# MCU.net
KiCad netlist of a schematic drawn in Altium Designer
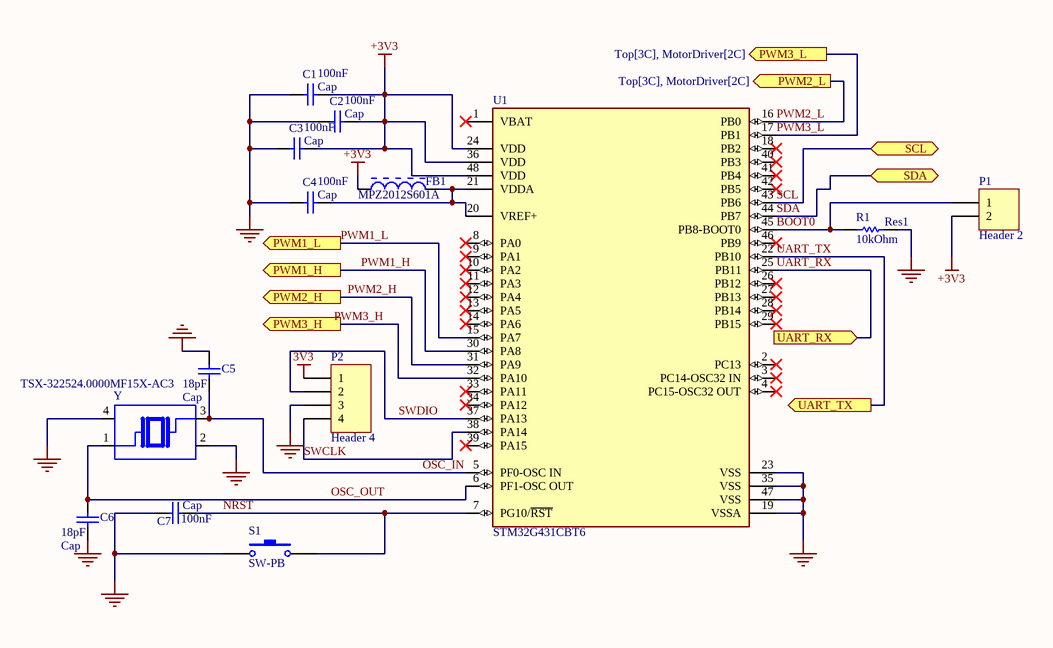
[diagram p0: MCU.SchDoc]

(export (version "E")
  (design (tool "Eeschema 10.0.6"))
  (components
    (comp (ref "C1")
      (value "Cap")
      (footprint "RAD-0.3")
      (description "Capacitor")
      (fields (field (name "ALTIUM_VALUE") "100nF") (field (name "PUBLISHER") "Altium Limited"))
      (libsource (lib "Miscellaneous Devices") (part "Cap"))
    )
    (comp (ref "C2")
      (value "Cap")
      (footprint "RAD-0.3")
      (description "Capacitor")
      (fields (field (name "ALTIUM_VALUE") "100nF") (field (name "PUBLISHER") "Altium Limited"))
      (libsource (lib "Miscellaneous Devices") (part "Cap"))
    )
    (comp (ref "C3")
      (value "Cap")
      (footprint "RAD-0.3")
      (description "Capacitor")
      (fields (field (name "ALTIUM_VALUE") "100nF") (field (name "PUBLISHER") "Altium Limited"))
      (libsource (lib "Miscellaneous Devices") (part "Cap"))
    )
    (comp (ref "C4")
      (value "Cap")
      (footprint "RAD-0.3")
      (description "Capacitor")
      (fields (field (name "ALTIUM_VALUE") "100nF") (field (name "PUBLISHER") "Altium Limited"))
      (libsource (lib "Miscellaneous Devices") (part "Cap"))
    )
    (comp (ref "C5")
      (value "Cap")
      (footprint "RAD-0.3")
      (description "Capacitor")
      (fields (field (name "ALTIUM_VALUE") "18pF") (field (name "PUBLISHER") "Altium Limited"))
      (libsource (lib "Miscellaneous Devices") (part "Cap"))
    )
    (comp (ref "C6")
      (value "Cap")
      (footprint "RAD-0.3")
      (description "Capacitor")
      (fields (field (name "ALTIUM_VALUE") "18pF") (field (name "PUBLISHER") "Altium Limited"))
      (libsource (lib "Miscellaneous Devices") (part "Cap"))
    )
    (comp (ref "C7")
      (value "Cap")
      (footprint "RAD-0.3")
      (description "Capacitor")
      (fields (field (name "ALTIUM_VALUE") "100nF") (field (name "PUBLISHER") "Altium Limited"))
      (libsource (lib "Miscellaneous Devices") (part "Cap"))
    )
    (comp (ref "FB1")
      (value "MPZ2012S601A")
      (footprint "TDK-MPZ2012_V")
      (fields (field (name "TOLERANCE") "25%") (field (name "MANUFACTURER") "TDK"))
      (libsource (lib "Altium Content Vault") (part "BEAD-2"))
    )
    (comp (ref "P1")
      (value "Header 2")
      (footprint "HDR1X2")
      (description "Header, 2-Pin")
      (fields (field (name "PUBLISHER") "Altium Limited"))
      (libsource (lib "Miscellaneous Connectors") (part "Header 2"))
    )
    (comp (ref "P2")
      (value "Header 4")
      (footprint "HDR1X4")
      (description "Header, 4-Pin")
      (fields (field (name "PUBLISHER") "Altium Limited"))
      (libsource (lib "Miscellaneous Connectors") (part "Header 4"))
    )
    (comp (ref "R1")
      (value "Res1")
      (footprint "AXIAL-0.3")
      (description "Resistor")
      (fields (field (name "ALTIUM_VALUE") "10kOhm") (field (name "PUBLISHER") "Altium Limited"))
      (libsource (lib "Miscellaneous Devices") (part "Res1"))
    )
    (comp (ref "S1")
      (value "SW-PB")
      (footprint "SPST-2")
      (description "Switch")
      (fields (field (name "PUBLISHER") "Altium Limited"))
      (libsource (lib "Miscellaneous Devices") (part "SW-PB"))
    )
    (comp (ref "U1")
      (value "STM32G431CBT6")
      (footprint "FP-LQFP48-5B-MFG")
      (description "MAINSTREAM ARM CORTEX-M4+ MCU 17")
      (fields
        (field (name "MANUFACTURER") "STMicroelectronics")
        (field (name "OCTOPART") "https://octopart.com/stm32g431cbt6-stmicroelectronics-98835224")
      )
      (libsource (lib "Altium Content Vault") (part "08b09c1d51ec08ade740842f2b8671b"))
    )
    (comp (ref "Y")
      (value "TSX-322524.0000MF15X-AC3")
      (footprint "OSCCC320X250X60")
      (description "24MHz Â±10ppm Crystal 9pF 40 Ohms 4-SMD, No Lead")
      (fields (field (name "MF") "EPSON") (field (name "MP") "TSX-3225 24.0000MF15X-AC3"))
      (libsource (lib "TSX-322524.0000MF15X-AC3") (part "TSX-322524.0000MF15X-AC3"))
    )
  )
  (nets
    (net (code "1") (name "+3V3") (class "Default")
      (node (ref "C1") (pin "2") (pinfunction "2_2") (pintype "passive"))
      (node (ref "C2") (pin "2") (pinfunction "2_2") (pintype "passive"))
      (node (ref "C3") (pin "2") (pinfunction "2_2") (pintype "passive"))
      (node (ref "FB1") (pin "1") (pinfunction "1_1") (pintype "passive"))
      (node (ref "P1") (pin "2") (pinfunction "2_2") (pintype "passive"))
      (node (ref "U1") (pin "24") (pinfunction "VDD_24") (pintype "power_in"))
      (node (ref "U1") (pin "36") (pinfunction "VDD_36") (pintype "power_in"))
      (node (ref "U1") (pin "48") (pinfunction "VDD_48") (pintype "power_in"))
    )
    (net (code "2") (name "/BOOT0") (class "Default")
      (node (ref "P1") (pin "1") (pinfunction "1_1") (pintype "passive"))
      (node (ref "R1") (pin "1") (pinfunction "1_1") (pintype "passive"))
      (node (ref "U1") (pin "45") (pinfunction "PB8-BOOT0_45") (pintype "bidirectional"))
    )
    (net (code "3") (name "/NRST") (class "Default")
      (node (ref "C7") (pin "2") (pinfunction "2_2") (pintype "passive"))
      (node (ref "S1") (pin "2") (pinfunction "2_2") (pintype "passive"))
      (node (ref "U1") (pin "7") (pinfunction "PG10/~{RST}_7") (pintype "bidirectional"))
    )
    (net (code "4") (name "/OSC_IN") (class "Default")
      (node (ref "C5") (pin "1") (pinfunction "1_1") (pintype "passive"))
      (node (ref "U1") (pin "5") (pinfunction "PF0-OSC_IN_5") (pintype "bidirectional"))
      (node (ref "Y") (pin "3") (pinfunction "3_3") (pintype "passive"))
    )
    (net (code "5") (name "/OSC_OUT") (class "Default")
      (node (ref "C6") (pin "2") (pinfunction "2_2") (pintype "passive"))
      (node (ref "U1") (pin "6") (pinfunction "PF1-OSC_OUT_6") (pintype "bidirectional"))
      (node (ref "Y") (pin "1") (pinfunction "1_1") (pintype "passive"))
    )
    (net (code "6") (name "/PWM1_H") (class "Default")
      (node (ref "U1") (pin "30") (pinfunction "PA8_30") (pintype "bidirectional"))
    )
    (net (code "7") (name "/PWM1_L") (class "Default")
      (node (ref "U1") (pin "15") (pinfunction "PA7_15") (pintype "bidirectional"))
    )
    (net (code "8") (name "/PWM2_H") (class "Default")
      (node (ref "U1") (pin "31") (pinfunction "PA9_31") (pintype "bidirectional"))
    )
    (net (code "9") (name "/PWM2_L") (class "Default")
      (node (ref "U1") (pin "16") (pinfunction "PB0_16") (pintype "bidirectional"))
    )
    (net (code "10") (name "/PWM3_H") (class "Default")
      (node (ref "U1") (pin "32") (pinfunction "PA10_32") (pintype "bidirectional"))
    )
    (net (code "11") (name "/PWM3_L") (class "Default")
      (node (ref "U1") (pin "17") (pinfunction "PB1_17") (pintype "bidirectional"))
    )
    (net (code "12") (name "/SCL") (class "Default")
      (node (ref "U1") (pin "43") (pinfunction "PB6_43") (pintype "bidirectional"))
    )
    (net (code "13") (name "/SDA") (class "Default")
      (node (ref "U1") (pin "44") (pinfunction "PB7_44") (pintype "bidirectional"))
    )
    (net (code "14") (name "/SWCLK") (class "Default")
      (node (ref "P2") (pin "4") (pinfunction "4_4") (pintype "passive"))
      (node (ref "U1") (pin "38") (pinfunction "PA14_38") (pintype "bidirectional"))
    )
    (net (code "15") (name "/SWDIO") (class "Default")
      (node (ref "P2") (pin "2") (pinfunction "2_2") (pintype "passive"))
      (node (ref "U1") (pin "37") (pinfunction "PA13_37") (pintype "bidirectional"))
    )
    (net (code "16") (name "/UART_RX") (class "Default")
      (node (ref "U1") (pin "25") (pinfunction "PB11_25") (pintype "bidirectional"))
    )
    (net (code "17") (name "/UART_TX") (class "Default")
      (node (ref "U1") (pin "22") (pinfunction "PB10_22") (pintype "bidirectional"))
    )
    (net (code "18") (name "3V3") (class "Default")
      (node (ref "P2") (pin "1") (pinfunction "1_1") (pintype "passive"))
    )
    (net (code "19") (name "<NO NET>") (class "Default")
      (node (ref "C1") (pin "1") (pinfunction "1_1") (pintype "passive"))
      (node (ref "C2") (pin "1") (pinfunction "1_1") (pintype "passive"))
      (node (ref "C3") (pin "1") (pinfunction "1_1") (pintype "passive"))
      (node (ref "C4") (pin "1") (pinfunction "1_1") (pintype "passive"))
      (node (ref "C5") (pin "2") (pinfunction "2_2") (pintype "passive"))
      (node (ref "C6") (pin "1") (pinfunction "1_1") (pintype "passive"))
      (node (ref "C7") (pin "1") (pinfunction "1_1") (pintype "passive"))
      (node (ref "P2") (pin "3") (pinfunction "3_3") (pintype "passive"))
      (node (ref "R1") (pin "2") (pinfunction "2_2") (pintype "passive"))
      (node (ref "S1") (pin "1") (pinfunction "1_1") (pintype "passive"))
      (node (ref "U1") (pin "19") (pinfunction "VSSA_19") (pintype "power_in"))
      (node (ref "U1") (pin "23") (pinfunction "VSS_23") (pintype "power_in"))
      (node (ref "U1") (pin "35") (pinfunction "VSS_35") (pintype "power_in"))
      (node (ref "U1") (pin "47") (pinfunction "VSS_47") (pintype "power_in"))
      (node (ref "Y") (pin "2") (pinfunction "2_2") (pintype "passive"))
      (node (ref "Y") (pin "4") (pinfunction "4_4") (pintype "passive"))
    )
    (net (code "20") (name "Net-(U1-VDDA)") (class "Default")
      (node (ref "C4") (pin "2") (pinfunction "2_2") (pintype "passive"))
      (node (ref "FB1") (pin "2") (pinfunction "2_2") (pintype "passive"))
      (node (ref "U1") (pin "20") (pinfunction "VREF+_20") (pintype "power_in"))
      (node (ref "U1") (pin "21") (pinfunction "VDDA_21") (pintype "power_in"))
    )
    (net (code "21") (name "unconnected-(U1-PA0-Pad8)") (class "Default")
      (node (ref "U1") (pin "8") (pinfunction "PA0_8") (pintype "bidirectional+no_connect"))
    )
    (net (code "22") (name "unconnected-(U1-PA1-Pad9)") (class "Default")
      (node (ref "U1") (pin "9") (pinfunction "PA1_9") (pintype "bidirectional+no_connect"))
    )
    (net (code "23") (name "unconnected-(U1-PA2-Pad10)") (class "Default")
      (node (ref "U1") (pin "10") (pinfunction "PA2_10") (pintype "bidirectional+no_connect"))
    )
    (net (code "24") (name "unconnected-(U1-PA3-Pad11)") (class "Default")
      (node (ref "U1") (pin "11") (pinfunction "PA3_11") (pintype "bidirectional+no_connect"))
    )
    (net (code "25") (name "unconnected-(U1-PA4-Pad12)") (class "Default")
      (node (ref "U1") (pin "12") (pinfunction "PA4_12") (pintype "bidirectional+no_connect"))
    )
    (net (code "26") (name "unconnected-(U1-PA5-Pad13)") (class "Default")
      (node (ref "U1") (pin "13") (pinfunction "PA5_13") (pintype "bidirectional+no_connect"))
    )
    (net (code "27") (name "unconnected-(U1-PA6-Pad14)") (class "Default")
      (node (ref "U1") (pin "14") (pinfunction "PA6_14") (pintype "bidirectional+no_connect"))
    )
    (net (code "28") (name "unconnected-(U1-PA11-Pad33)") (class "Default")
      (node (ref "U1") (pin "33") (pinfunction "PA11_33") (pintype "bidirectional+no_connect"))
    )
    (net (code "29") (name "unconnected-(U1-PA12-Pad34)") (class "Default")
      (node (ref "U1") (pin "34") (pinfunction "PA12_34") (pintype "bidirectional+no_connect"))
    )
    (net (code "30") (name "unconnected-(U1-PA15-Pad39)") (class "Default")
      (node (ref "U1") (pin "39") (pinfunction "PA15_39") (pintype "bidirectional+no_connect"))
    )
    (net (code "31") (name "unconnected-(U1-PB2-Pad18)") (class "Default")
      (node (ref "U1") (pin "18") (pinfunction "PB2_18") (pintype "bidirectional+no_connect"))
    )
    (net (code "32") (name "unconnected-(U1-PB3-Pad40)") (class "Default")
      (node (ref "U1") (pin "40") (pinfunction "PB3_40") (pintype "bidirectional+no_connect"))
    )
    (net (code "33") (name "unconnected-(U1-PB4-Pad41)") (class "Default")
      (node (ref "U1") (pin "41") (pinfunction "PB4_41") (pintype "bidirectional+no_connect"))
    )
    (net (code "34") (name "unconnected-(U1-PB5-Pad42)") (class "Default")
      (node (ref "U1") (pin "42") (pinfunction "PB5_42") (pintype "bidirectional+no_connect"))
    )
    (net (code "35") (name "unconnected-(U1-PB9-Pad46)") (class "Default")
      (node (ref "U1") (pin "46") (pinfunction "PB9_46") (pintype "bidirectional+no_connect"))
    )
    (net (code "36") (name "unconnected-(U1-PB12-Pad26)") (class "Default")
      (node (ref "U1") (pin "26") (pinfunction "PB12_26") (pintype "bidirectional+no_connect"))
    )
    (net (code "37") (name "unconnected-(U1-PB13-Pad27)") (class "Default")
      (node (ref "U1") (pin "27") (pinfunction "PB13_27") (pintype "bidirectional+no_connect"))
    )
    (net (code "38") (name "unconnected-(U1-PB14-Pad28)") (class "Default")
      (node (ref "U1") (pin "28") (pinfunction "PB14_28") (pintype "bidirectional+no_connect"))
    )
    (net (code "39") (name "unconnected-(U1-PB15-Pad29)") (class "Default")
      (node (ref "U1") (pin "29") (pinfunction "PB15_29") (pintype "bidirectional+no_connect"))
    )
    (net (code "40") (name "unconnected-(U1-PC13-Pad2)") (class "Default")
      (node (ref "U1") (pin "2") (pinfunction "PC13_2") (pintype "bidirectional+no_connect"))
    )
    (net (code "41") (name "unconnected-(U1-PC14-OSC32_IN-Pad3)") (class "Default")
      (node (ref "U1") (pin "3") (pinfunction "PC14-OSC32_IN_3") (pintype "bidirectional+no_connect"))
    )
    (net (code "42") (name "unconnected-(U1-PC15-OSC32_OUT-Pad4)") (class "Default")
      (node (ref "U1") (pin "4") (pinfunction "PC15-OSC32_OUT_4") (pintype "bidirectional+no_connect"))
    )
    (net (code "43") (name "unconnected-(U1-VBAT-Pad1)") (class "Default")
      (node (ref "U1") (pin "1") (pinfunction "VBAT_1") (pintype "power_in+no_connect"))
    )
  )
)
